# 01.net
KiCad netlist of a schematic drawn in EAGLE
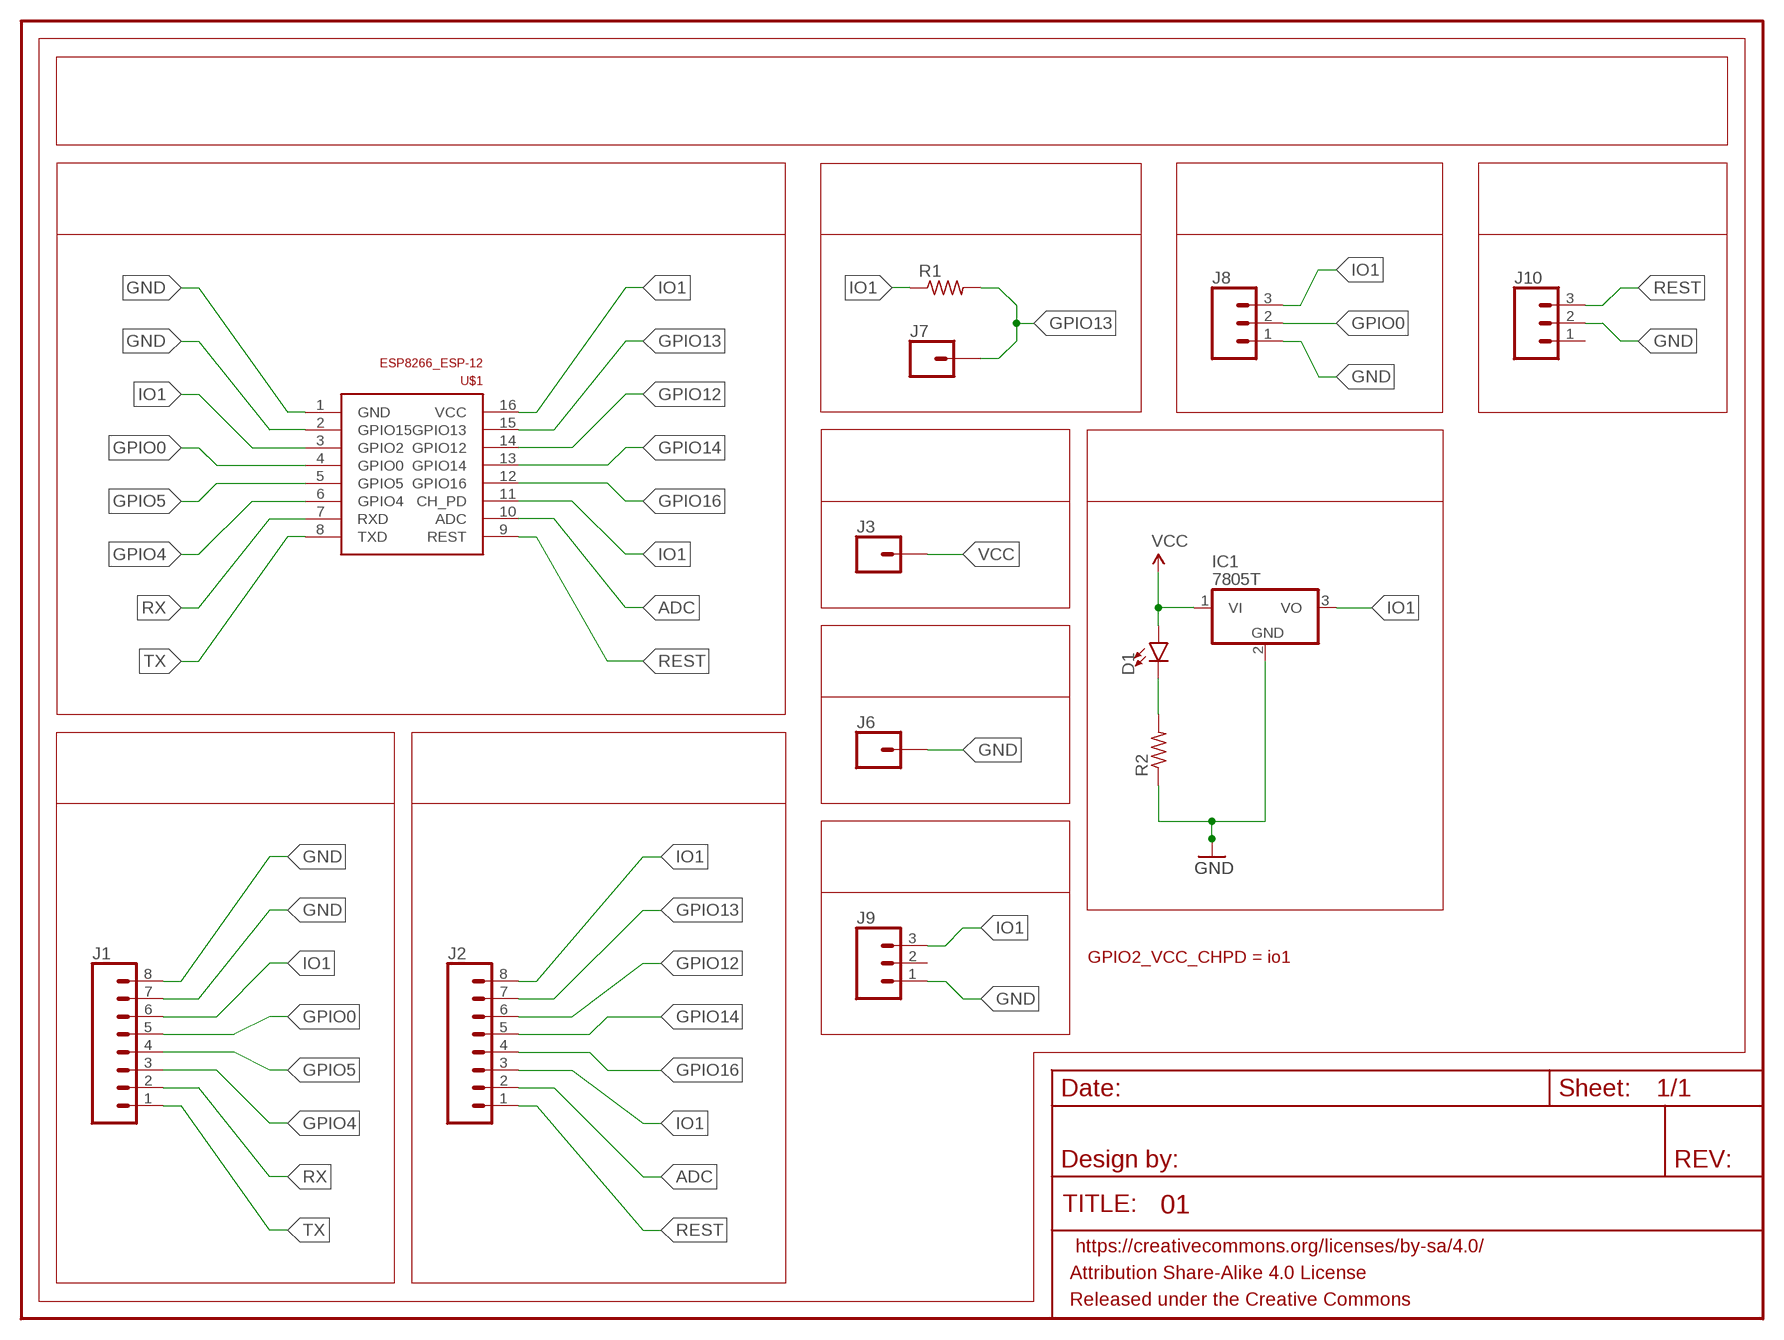
[diagram p0: schematic, sheet 1]

(export (version "E")
  (design (tool "Eeschema 10.0.6"))
  (components
    (comp (ref "D1")
      (value "LED5MM")
      (footprint "eagle-import:LED_5MM")
      (libsource (lib "eagle-import") (part "LED5MM"))
    )
    (comp (ref "FRAME1")
      (value "FRAME-LETTER")
      (footprint "eagle-import:CREATIVE_COMMONS")
      (libsource (lib "eagle-import") (part "FRAME-LETTER"))
    )
    (comp (ref "IC1")
      (value "7805T")
      (footprint "eagle-import:TO220H")
      (libsource (lib "eagle-import") (part "78T05"))
    )
    (comp (ref "J1")
      (value "CONN_08LONGPADS")
      (footprint "eagle-import:1X08_LONGPADS")
      (libsource (lib "eagle-import") (part "CONN_08LONGPADS"))
    )
    (comp (ref "J2")
      (value "CONN_08LONGPADS")
      (footprint "eagle-import:1X08_LONGPADS")
      (libsource (lib "eagle-import") (part "CONN_08LONGPADS"))
    )
    (comp (ref "J3")
      (value "CONN_01PTH_LONGPAD")
      (footprint "eagle-import:1X01_LONGPAD")
      (libsource (lib "eagle-import") (part "CONN_01PTH_LONGPAD"))
    )
    (comp (ref "J6")
      (value "CONN_01PTH_LONGPAD")
      (footprint "eagle-import:1X01_LONGPAD")
      (libsource (lib "eagle-import") (part "CONN_01PTH_LONGPAD"))
    )
    (comp (ref "J7")
      (value "CONN_01PTH_LONGPAD")
      (footprint "eagle-import:1X01_LONGPAD")
      (libsource (lib "eagle-import") (part "CONN_01PTH_LONGPAD"))
    )
    (comp (ref "J8")
      (value "CONN_03LONGPADS")
      (footprint "eagle-import:1X03_LONGPADS")
      (libsource (lib "eagle-import") (part "CONN_03LONGPADS"))
    )
    (comp (ref "J9")
      (value "CONN_03LONGPADS")
      (footprint "eagle-import:1X03_LONGPADS")
      (libsource (lib "eagle-import") (part "CONN_03LONGPADS"))
    )
    (comp (ref "J10")
      (value "CONN_03LONGPADS")
      (footprint "eagle-import:1X03_LONGPADS")
      (libsource (lib "eagle-import") (part "CONN_03LONGPADS"))
    )
    (comp (ref "R1")
      (value "R-US_0204/7")
      (footprint "eagle-import:0204_7")
      (libsource (lib "eagle-import") (part "R-US_0204/7"))
    )
    (comp (ref "R2")
      (value "R-US_0204/7")
      (footprint "eagle-import:0204_7")
      (libsource (lib "eagle-import") (part "R-US_0204/7"))
    )
    (comp (ref "U$1")
      (value "ESP8266_ESP-12")
      (footprint "eagle-import:ESP8266-ESP12")
      (libsource (lib "eagle-import") (part "ESP8266_ESP-12"))
    )
  )
  (nets
    (net (code "1") (name "ADC") (class "Default")
      (node (ref "J2") (pin "2") (pinfunction "2_2") (pintype "passive"))
      (node (ref "U$1") (pin "10") (pinfunction "ADC_10") (pintype "bidirectional"))
    )
    (net (code "2") (name "GND") (class "Default")
      (node (ref "IC1") (pin "2") (pinfunction "GND_2") (pintype "passive"))
      (node (ref "J1") (pin "7") (pinfunction "7_7") (pintype "passive"))
      (node (ref "J1") (pin "8") (pinfunction "8_8") (pintype "passive"))
      (node (ref "J10") (pin "2") (pinfunction "2_2") (pintype "passive"))
      (node (ref "J6") (pin "1") (pinfunction "1_1") (pintype "passive"))
      (node (ref "J8") (pin "1") (pinfunction "1_1") (pintype "passive"))
      (node (ref "J9") (pin "1") (pinfunction "1_1") (pintype "passive"))
      (node (ref "R2") (pin "1") (pinfunction "1_1") (pintype "passive"))
      (node (ref "U$1") (pin "1") (pinfunction "GND_1") (pintype "bidirectional"))
      (node (ref "U$1") (pin "2") (pinfunction "GPIO15_2") (pintype "bidirectional"))
    )
    (net (code "3") (name "GPIO0") (class "Default")
      (node (ref "J1") (pin "5") (pinfunction "5_5") (pintype "passive"))
      (node (ref "J8") (pin "2") (pinfunction "2_2") (pintype "passive"))
      (node (ref "U$1") (pin "4") (pinfunction "GPIO0_4") (pintype "bidirectional"))
    )
    (net (code "4") (name "GPIO4") (class "Default")
      (node (ref "J1") (pin "3") (pinfunction "3_3") (pintype "passive"))
      (node (ref "U$1") (pin "6") (pinfunction "GPIO4_6") (pintype "bidirectional"))
    )
    (net (code "5") (name "GPIO5") (class "Default")
      (node (ref "J1") (pin "4") (pinfunction "4_4") (pintype "passive"))
      (node (ref "U$1") (pin "5") (pinfunction "GPIO5_5") (pintype "bidirectional"))
    )
    (net (code "6") (name "GPIO12") (class "Default")
      (node (ref "J2") (pin "6") (pinfunction "6_6") (pintype "passive"))
      (node (ref "U$1") (pin "14") (pinfunction "GPIO12_14") (pintype "bidirectional"))
    )
    (net (code "7") (name "GPIO13") (class "Default")
      (node (ref "J2") (pin "7") (pinfunction "7_7") (pintype "passive"))
      (node (ref "J7") (pin "1") (pinfunction "1_1") (pintype "passive"))
      (node (ref "R1") (pin "2") (pinfunction "2_2") (pintype "passive"))
      (node (ref "U$1") (pin "15") (pinfunction "GPIO13_15") (pintype "bidirectional"))
    )
    (net (code "8") (name "GPIO14") (class "Default")
      (node (ref "J2") (pin "5") (pinfunction "5_5") (pintype "passive"))
      (node (ref "U$1") (pin "13") (pinfunction "GPIO14_13") (pintype "bidirectional"))
    )
    (net (code "9") (name "GPIO16") (class "Default")
      (node (ref "J2") (pin "4") (pinfunction "4_4") (pintype "passive"))
      (node (ref "U$1") (pin "12") (pinfunction "GPIO16_12") (pintype "bidirectional"))
    )
    (net (code "10") (name "IO1") (class "Default")
      (node (ref "IC1") (pin "3") (pinfunction "VO_3") (pintype "passive"))
      (node (ref "J1") (pin "6") (pinfunction "6_6") (pintype "passive"))
      (node (ref "J2") (pin "3") (pinfunction "3_3") (pintype "passive"))
      (node (ref "J2") (pin "8") (pinfunction "8_8") (pintype "passive"))
      (node (ref "J8") (pin "3") (pinfunction "3_3") (pintype "passive"))
      (node (ref "J9") (pin "3") (pinfunction "3_3") (pintype "passive"))
      (node (ref "R1") (pin "1") (pinfunction "1_1") (pintype "passive"))
      (node (ref "U$1") (pin "11") (pinfunction "CH_PD_11") (pintype "bidirectional"))
      (node (ref "U$1") (pin "16") (pinfunction "VCC_16") (pintype "bidirectional"))
      (node (ref "U$1") (pin "3") (pinfunction "GPIO2_3") (pintype "bidirectional"))
    )
    (net (code "11") (name "Net-(D1-C)") (class "Default")
      (node (ref "D1") (pin "K") (pinfunction "C_K") (pintype "passive"))
      (node (ref "R2") (pin "2") (pinfunction "2_2") (pintype "passive"))
    )
    (net (code "12") (name "REST") (class "Default")
      (node (ref "J10") (pin "3") (pinfunction "3_3") (pintype "passive"))
      (node (ref "J2") (pin "1") (pinfunction "1_1") (pintype "passive"))
      (node (ref "U$1") (pin "9") (pinfunction "REST_9") (pintype "bidirectional"))
    )
    (net (code "13") (name "RX") (class "Default")
      (node (ref "J1") (pin "2") (pinfunction "2_2") (pintype "passive"))
      (node (ref "U$1") (pin "7") (pinfunction "RXD_7") (pintype "bidirectional"))
    )
    (net (code "14") (name "TX") (class "Default")
      (node (ref "J1") (pin "1") (pinfunction "1_1") (pintype "passive"))
      (node (ref "U$1") (pin "8") (pinfunction "TXD_8") (pintype "bidirectional"))
    )
    (net (code "15") (name "VCC") (class "Default")
      (node (ref "D1") (pin "A") (pinfunction "A_A") (pintype "passive"))
      (node (ref "IC1") (pin "1") (pinfunction "VI_1") (pintype "input"))
      (node (ref "J3") (pin "1") (pinfunction "1_1") (pintype "passive"))
    )
    (net (code "16") (name "unconnected-(J9-Pad2)") (class "Default")
      (node (ref "J9") (pin "2") (pinfunction "2_2") (pintype "passive"))
    )
    (net (code "17") (name "unconnected-(J10-Pad1)") (class "Default")
      (node (ref "J10") (pin "1") (pinfunction "1_1") (pintype "passive"))
    )
  )
)
